# LED_Matrix_Driver_HT16K33_v1_0.net
KiCad netlist of a schematic drawn in EAGLE
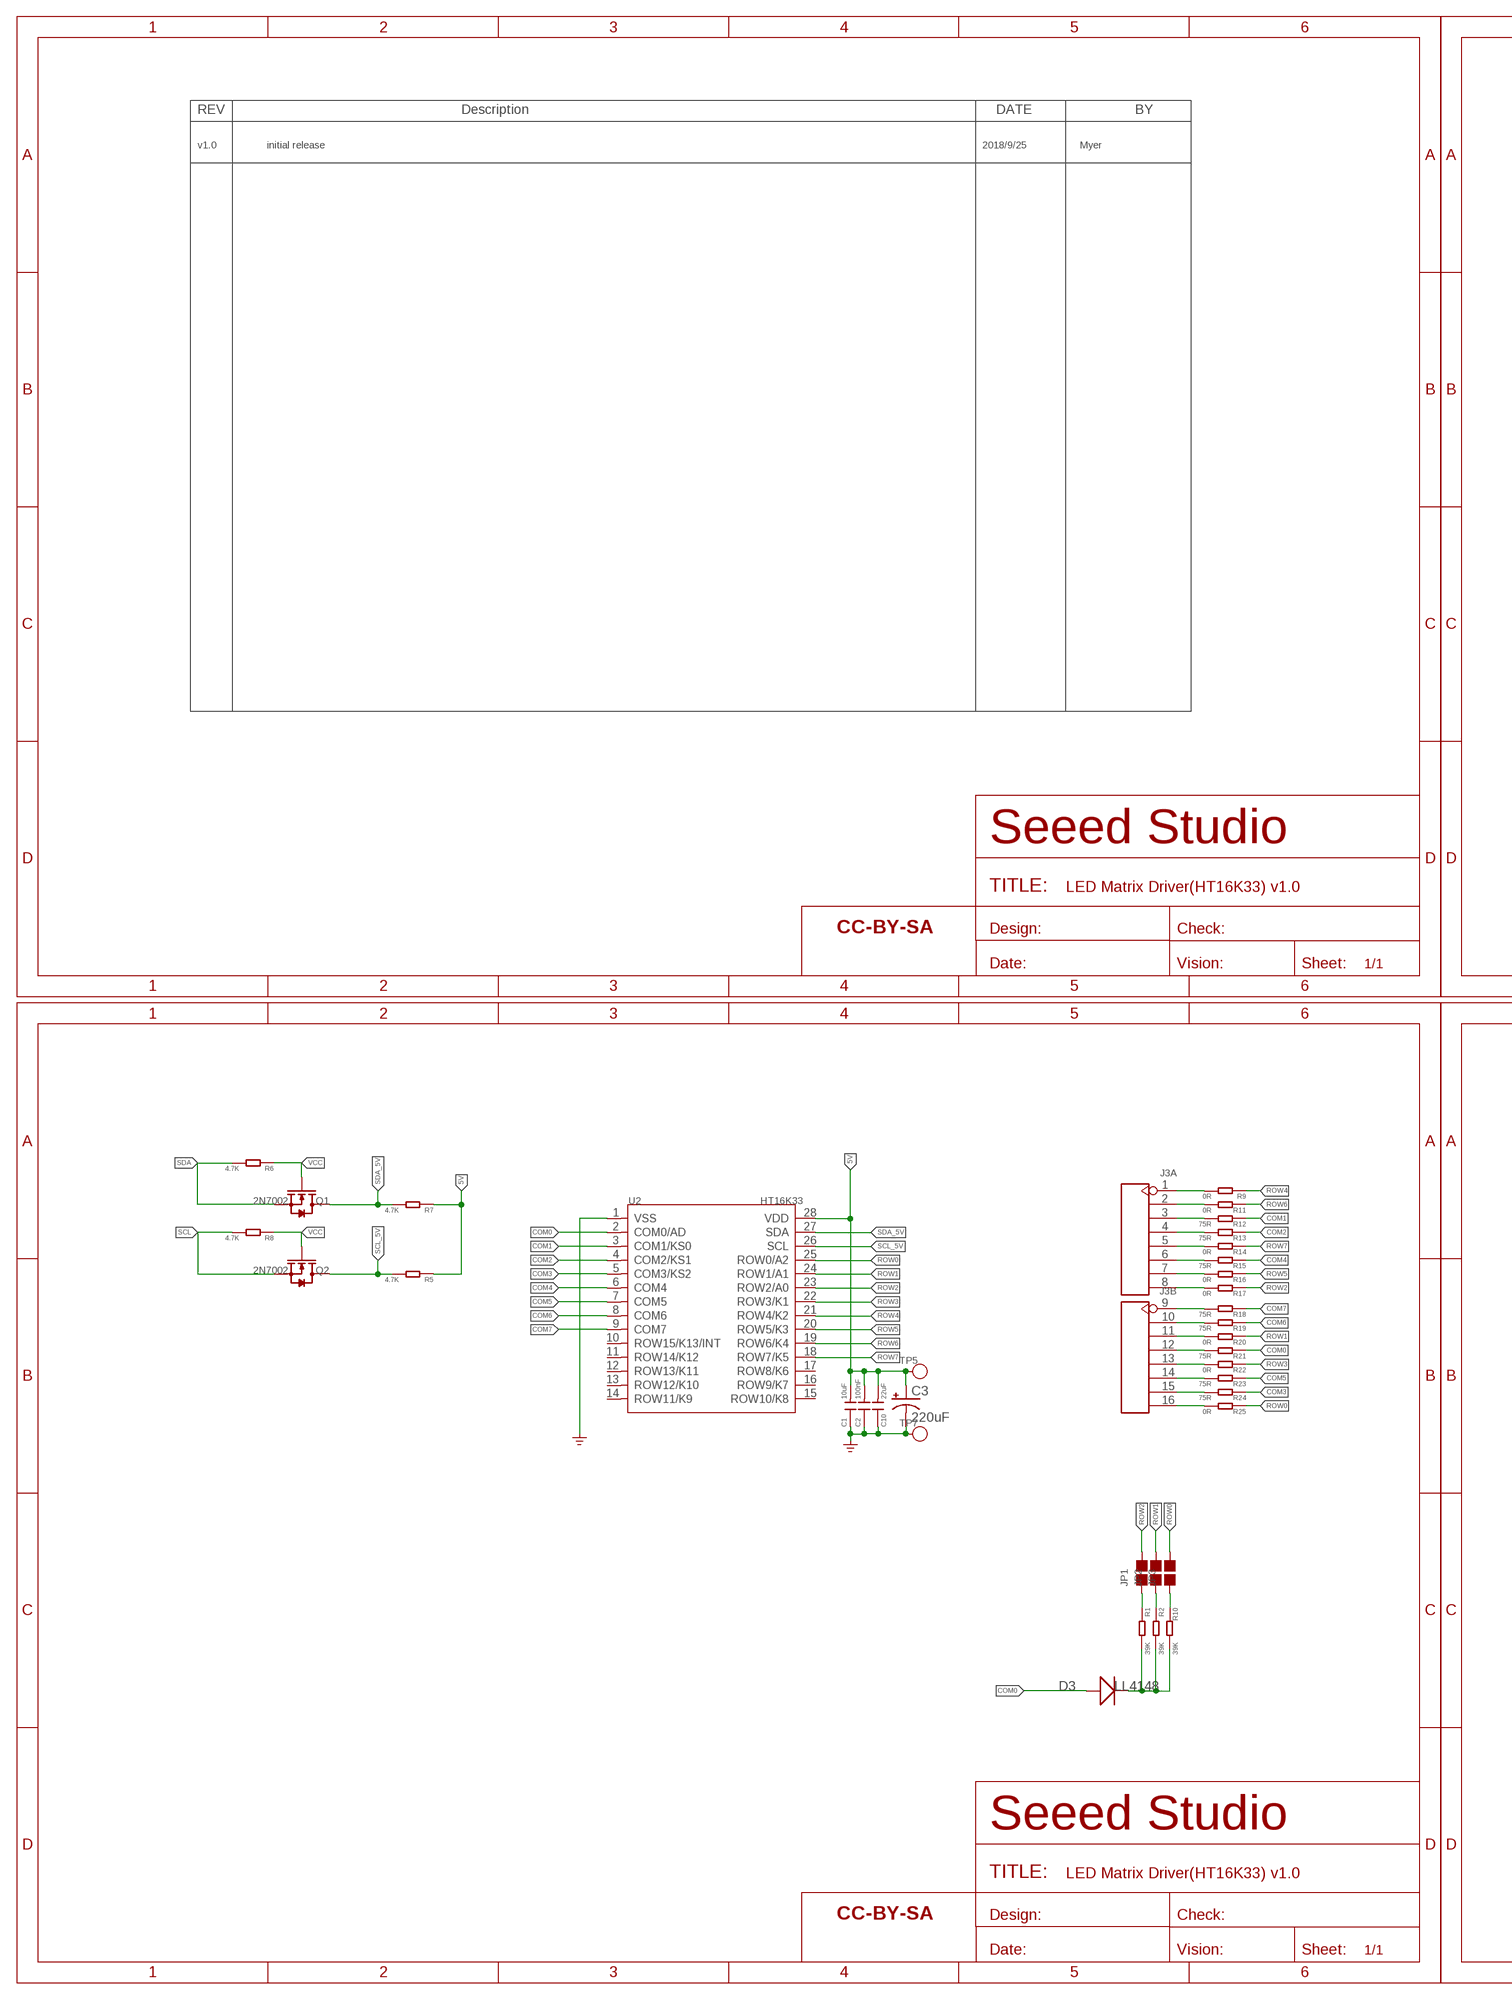
[diagram p0: schematic, sheet 1, part 1 of 2]
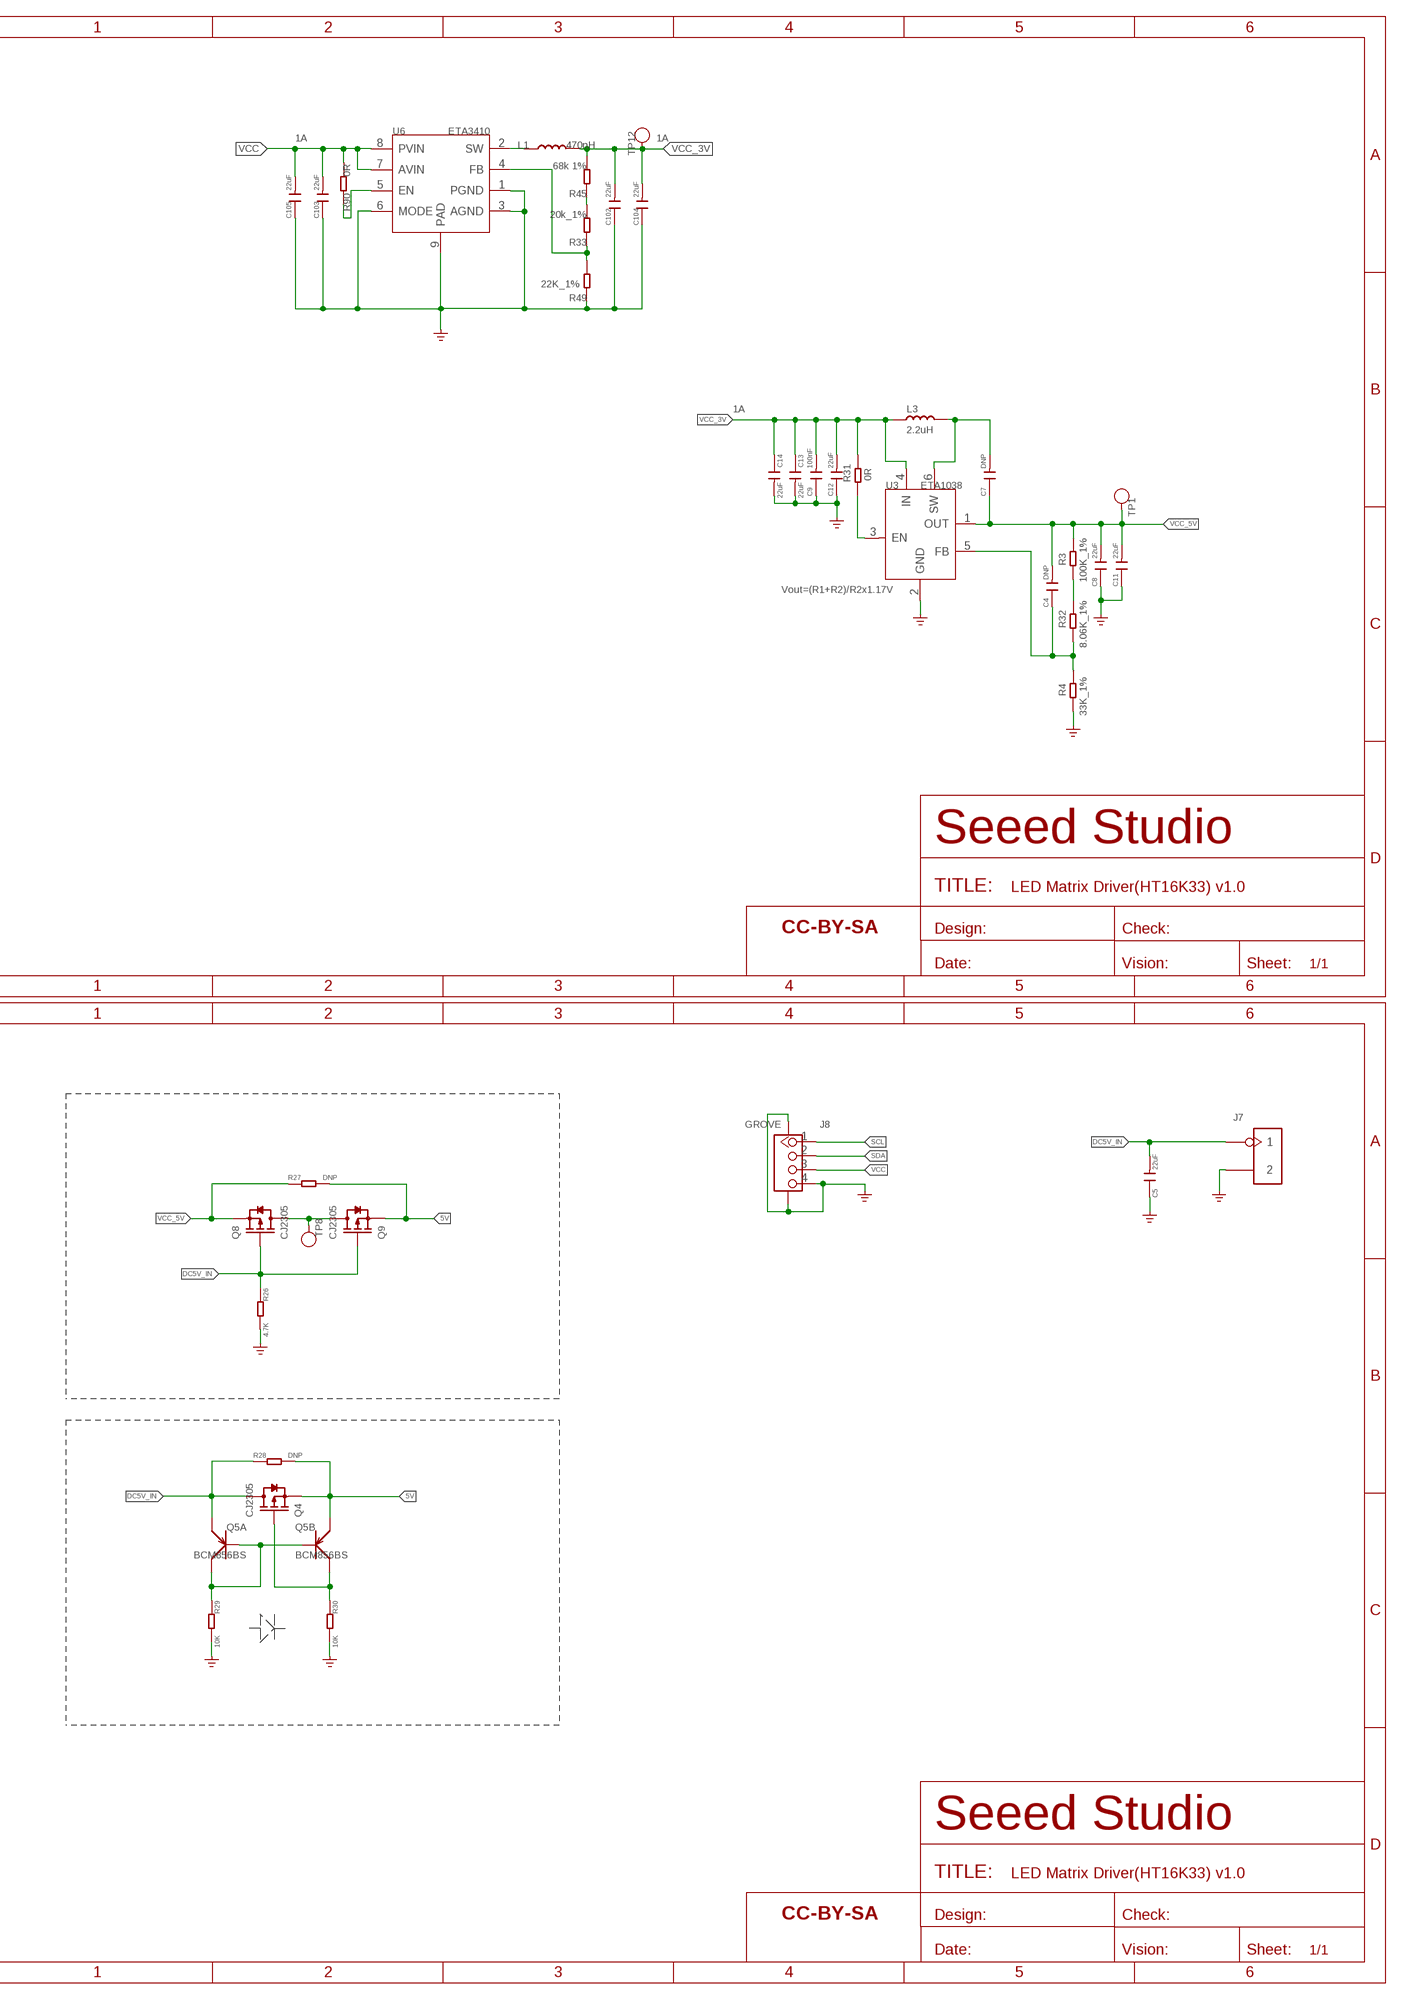
[diagram p1: schematic, sheet 1, part 2 of 2]

(export (version "E")
  (design (tool "Eeschema 10.0.6"))
  (components
    (comp (ref "C1")
      (value "10uF")
      (footprint "eagle-import:C0805")
      (libsource (lib "eagle-import") (part "C-0805"))
    )
    (comp (ref "C2")
      (value "100nF")
      (footprint "eagle-import:C0603")
      (libsource (lib "eagle-import") (part "C-0603"))
    )
    (comp (ref "C3")
      (value "220uF")
      (footprint "eagle-import:PANASONIC_D")
      (libsource (lib "eagle-import") (part "CPOL-USD"))
    )
    (comp (ref "C4")
      (value "DNP")
      (footprint "eagle-import:C0603")
      (libsource (lib "eagle-import") (part "C-0603"))
    )
    (comp (ref "C5")
      (value "22uF")
      (footprint "eagle-import:C0805")
      (libsource (lib "eagle-import") (part "C-0805"))
    )
    (comp (ref "C7")
      (value "DNP")
      (footprint "eagle-import:C0603")
      (libsource (lib "eagle-import") (part "C-0603"))
    )
    (comp (ref "C8")
      (value "22uF")
      (footprint "eagle-import:C0603")
      (libsource (lib "eagle-import") (part "C-0603"))
    )
    (comp (ref "C9")
      (value "100nF")
      (footprint "eagle-import:C0603")
      (libsource (lib "eagle-import") (part "C-0603"))
    )
    (comp (ref "C10")
      (value "22uF")
      (footprint "eagle-import:C0805")
      (libsource (lib "eagle-import") (part "C-0805"))
    )
    (comp (ref "C11")
      (value "22uF")
      (footprint "eagle-import:C0603")
      (libsource (lib "eagle-import") (part "C-0603"))
    )
    (comp (ref "C12")
      (value "22uF")
      (footprint "eagle-import:C0603")
      (libsource (lib "eagle-import") (part "C-0603"))
    )
    (comp (ref "C13")
      (value "22uF")
      (footprint "eagle-import:C0603")
      (libsource (lib "eagle-import") (part "C-0603"))
    )
    (comp (ref "C14")
      (value "22uF")
      (footprint "eagle-import:C0603")
      (libsource (lib "eagle-import") (part "C-0603"))
    )
    (comp (ref "C102")
      (value "22uF")
      (footprint "eagle-import:C0603")
      (libsource (lib "eagle-import") (part "C-0603"))
    )
    (comp (ref "C103")
      (value "22uF")
      (footprint "eagle-import:C0603")
      (libsource (lib "eagle-import") (part "C-0603"))
    )
    (comp (ref "C104")
      (value "22uF")
      (footprint "eagle-import:C0603")
      (libsource (lib "eagle-import") (part "C-0603"))
    )
    (comp (ref "C105")
      (value "22uF")
      (footprint "eagle-import:C0603")
      (libsource (lib "eagle-import") (part "C-0603"))
    )
    (comp (ref "D3")
      (value "LL4148")
      (footprint "eagle-import:DO-35-SMD")
      (libsource (lib "eagle-import") (part "D'1N4148-SMD'"))
    )
    (comp (ref "FR1")
      (value "SEEEDSTUDIO-OPEN-SCH-FRAME")
      (footprint "eagle-import:SEEEDSTUDIO-PCB-FRAME")
      (libsource (lib "eagle-import") (part "SEEEDSTUDIO-OPEN-SCH-FRAME"))
    )
    (comp (ref "FR2")
      (value "SEEEDSTUDIO-OPEN-SCH-FRAME")
      (footprint "eagle-import:SEEEDSTUDIO-PCB-FRAME")
      (libsource (lib "eagle-import") (part "SEEEDSTUDIO-OPEN-SCH-FRAME"))
    )
    (comp (ref "FR3")
      (value "SEEEDSTUDIO-OPEN-SCH-FRAME")
      (footprint "eagle-import:SEEEDSTUDIO-PCB-FRAME")
      (libsource (lib "eagle-import") (part "SEEEDSTUDIO-OPEN-SCH-FRAME"))
    )
    (comp (ref "J3")
      (value "HEADER-1X8PX2-LED-28.5MM")
      (footprint "eagle-import:H8X2-SMD-2.54-28.5MM")
      (libsource (lib "eagle-import") (part "HEADER-1X8PX2-LED-28.5MM"))
    )
    (comp (ref "J7")
      (value "HEADER-2P-65/35MIL")
      (footprint "eagle-import:H2-2.54")
      (libsource (lib "eagle-import") (part "HEADER-2P-65/35MIL"))
    )
    (comp (ref "J8")
      (value "GROVE")
      (footprint "eagle-import:HW4-SMD-2.0")
      (libsource (lib "eagle-import") (part "GROVE-CONNECTOR-SMD'DD'"))
    )
    (comp (ref "JP1")
      (value "JP-2P-NO")
      (footprint "eagle-import:2P-SMD-NO")
      (libsource (lib "eagle-import") (part "JP-2P-NO"))
    )
    (comp (ref "JP2")
      (value "JP-2P-NO")
      (footprint "eagle-import:2P-SMD-NO")
      (libsource (lib "eagle-import") (part "JP-2P-NO"))
    )
    (comp (ref "JP3")
      (value "JP-2P-NO")
      (footprint "eagle-import:2P-SMD-NO")
      (libsource (lib "eagle-import") (part "JP-2P-NO"))
    )
    (comp (ref "L1")
      (value "470nH")
      (footprint "eagle-import:L201610")
      (libsource (lib "eagle-import") (part "L-MPM201610SR33_T"))
    )
    (comp (ref "L3")
      (value "2.2uH")
      (footprint "eagle-import:L0806")
      (libsource (lib "eagle-import") (part "INDUCTOR/FERRITE-BEAD'0806'"))
    )
    (comp (ref "Q1")
      (value "2N7002")
      (footprint "eagle-import:SOT-23")
      (libsource (lib "eagle-import") (part "MOSFET-N'SOT23'"))
    )
    (comp (ref "Q2")
      (value "2N7002")
      (footprint "eagle-import:SOT-23")
      (libsource (lib "eagle-import") (part "MOSFET-N'SOT23'"))
    )
    (comp (ref "Q4")
      (value "CJ2305")
      (footprint "eagle-import:SOT-23")
      (libsource (lib "eagle-import") (part "MOSFET-P'SI2323CDS/SI2305DS{lt}BR{gt}'"))
    )
    (comp (ref "Q5")
      (value "BCM856BS")
      (footprint "eagle-import:SOT-363")
      (libsource (lib "eagle-import") (part "TRANSISTOR-DUAL-PNP"))
    )
    (comp (ref "Q8")
      (value "CJ2305")
      (footprint "eagle-import:SOT-23")
      (libsource (lib "eagle-import") (part "MOSFET-P'SI2323CDS/SI2305DS{lt}BR{gt}'"))
    )
    (comp (ref "Q9")
      (value "CJ2305")
      (footprint "eagle-import:SOT-23")
      (libsource (lib "eagle-import") (part "MOSFET-P'SI2323CDS/SI2305DS{lt}BR{gt}'"))
    )
    (comp (ref "R1")
      (value "39K")
      (footprint "eagle-import:R0603")
      (libsource (lib "eagle-import") (part "R-0603"))
    )
    (comp (ref "R2")
      (value "39K")
      (footprint "eagle-import:R0603")
      (libsource (lib "eagle-import") (part "R-0603"))
    )
    (comp (ref "R3")
      (value "100K_1%")
      (footprint "eagle-import:R0603")
      (libsource (lib "eagle-import") (part "R-0603"))
    )
    (comp (ref "R4")
      (value "33K_1%")
      (footprint "eagle-import:R0603")
      (libsource (lib "eagle-import") (part "R-0603"))
    )
    (comp (ref "R5")
      (value "4.7K")
      (footprint "eagle-import:R0603")
      (libsource (lib "eagle-import") (part "R-0603"))
    )
    (comp (ref "R6")
      (value "4.7K")
      (footprint "eagle-import:R0603")
      (libsource (lib "eagle-import") (part "R-0603"))
    )
    (comp (ref "R7")
      (value "4.7K")
      (footprint "eagle-import:R0603")
      (libsource (lib "eagle-import") (part "R-0603"))
    )
    (comp (ref "R8")
      (value "4.7K")
      (footprint "eagle-import:R0603")
      (libsource (lib "eagle-import") (part "R-0603"))
    )
    (comp (ref "R9")
      (value "0R")
      (footprint "eagle-import:R0603")
      (libsource (lib "eagle-import") (part "R-0603"))
    )
    (comp (ref "R10")
      (value "39K")
      (footprint "eagle-import:R0603")
      (libsource (lib "eagle-import") (part "R-0603"))
    )
    (comp (ref "R11")
      (value "0R")
      (footprint "eagle-import:R0603")
      (libsource (lib "eagle-import") (part "R-0603"))
    )
    (comp (ref "R12")
      (value "75R")
      (footprint "eagle-import:R0603")
      (libsource (lib "eagle-import") (part "R-0603"))
    )
    (comp (ref "R13")
      (value "75R")
      (footprint "eagle-import:R0603")
      (libsource (lib "eagle-import") (part "R-0603"))
    )
    (comp (ref "R14")
      (value "0R")
      (footprint "eagle-import:R0603")
      (libsource (lib "eagle-import") (part "R-0603"))
    )
    (comp (ref "R15")
      (value "75R")
      (footprint "eagle-import:R0603")
      (libsource (lib "eagle-import") (part "R-0603"))
    )
    (comp (ref "R16")
      (value "0R")
      (footprint "eagle-import:R0603")
      (libsource (lib "eagle-import") (part "R-0603"))
    )
    (comp (ref "R17")
      (value "0R")
      (footprint "eagle-import:R0603")
      (libsource (lib "eagle-import") (part "R-0603"))
    )
    (comp (ref "R18")
      (value "75R")
      (footprint "eagle-import:R0603")
      (libsource (lib "eagle-import") (part "R-0603"))
    )
    (comp (ref "R19")
      (value "75R")
      (footprint "eagle-import:R0603")
      (libsource (lib "eagle-import") (part "R-0603"))
    )
    (comp (ref "R20")
      (value "0R")
      (footprint "eagle-import:R0603")
      (libsource (lib "eagle-import") (part "R-0603"))
    )
    (comp (ref "R21")
      (value "75R")
      (footprint "eagle-import:R0603")
      (libsource (lib "eagle-import") (part "R-0603"))
    )
    (comp (ref "R22")
      (value "0R")
      (footprint "eagle-import:R0603")
      (libsource (lib "eagle-import") (part "R-0603"))
    )
    (comp (ref "R23")
      (value "75R")
      (footprint "eagle-import:R0603")
      (libsource (lib "eagle-import") (part "R-0603"))
    )
    (comp (ref "R24")
      (value "75R")
      (footprint "eagle-import:R0603")
      (libsource (lib "eagle-import") (part "R-0603"))
    )
    (comp (ref "R25")
      (value "0R")
      (footprint "eagle-import:R0603")
      (libsource (lib "eagle-import") (part "R-0603"))
    )
    (comp (ref "R26")
      (value "4.7K")
      (footprint "eagle-import:R0603")
      (libsource (lib "eagle-import") (part "R-0603"))
    )
    (comp (ref "R27")
      (value "DNP")
      (footprint "eagle-import:R0603")
      (libsource (lib "eagle-import") (part "R-0603"))
    )
    (comp (ref "R28")
      (value "DNP")
      (footprint "eagle-import:R0603")
      (libsource (lib "eagle-import") (part "R-0603"))
    )
    (comp (ref "R29")
      (value "10K")
      (footprint "eagle-import:R0603")
      (libsource (lib "eagle-import") (part "R-0603"))
    )
    (comp (ref "R30")
      (value "10K")
      (footprint "eagle-import:R0603")
      (libsource (lib "eagle-import") (part "R-0603"))
    )
    (comp (ref "R31")
      (value "0R")
      (footprint "eagle-import:R0603")
      (libsource (lib "eagle-import") (part "R-0603"))
    )
    (comp (ref "R32")
      (value "8.06K_1%")
      (footprint "eagle-import:R0603")
      (libsource (lib "eagle-import") (part "R-0603"))
    )
    (comp (ref "R33")
      (value "20k_1%")
      (footprint "eagle-import:R0603")
      (libsource (lib "eagle-import") (part "R-0603"))
    )
    (comp (ref "R45")
      (value "68k 1%")
      (footprint "eagle-import:R0603")
      (libsource (lib "eagle-import") (part "R-0603"))
    )
    (comp (ref "R49")
      (value "22K_1%")
      (footprint "eagle-import:R0603")
      (libsource (lib "eagle-import") (part "R-0603"))
    )
    (comp (ref "R90")
      (value "0R")
      (footprint "eagle-import:R0603")
      (libsource (lib "eagle-import") (part "R-0603"))
    )
    (comp (ref "TP1")
      (value "TEST-POINT'4545'")
      (footprint "eagle-import:TP-D45MIL")
      (fields (field (name "PARTNO") "DNP"))
      (libsource (lib "eagle-import") (part "TEST-POINT'4545'"))
    )
    (comp (ref "TP5")
      (value "TEST-POINT'4545'")
      (footprint "eagle-import:TP-D45MIL")
      (fields (field (name "PARTNO") "DNP"))
      (libsource (lib "eagle-import") (part "TEST-POINT'4545'"))
    )
    (comp (ref "TP7")
      (value "TEST-POINT'4545'")
      (footprint "eagle-import:TP-D45MIL")
      (fields (field (name "PARTNO") "DNP"))
      (libsource (lib "eagle-import") (part "TEST-POINT'4545'"))
    )
    (comp (ref "TP8")
      (value "TEST-POINT'4545'")
      (footprint "eagle-import:TP-D45MIL")
      (fields (field (name "PARTNO") "DNP"))
      (libsource (lib "eagle-import") (part "TEST-POINT'4545'"))
    )
    (comp (ref "TP12")
      (value "TEST-POINT'4545'")
      (footprint "eagle-import:TP-D45MIL")
      (fields (field (name "PARTNO") "DNP"))
      (libsource (lib "eagle-import") (part "TEST-POINT'4545'"))
    )
    (comp (ref "U$1")
      (value "SEEEDSTUDIO-OPEN-SCH-FRAME")
      (footprint "eagle-import:SEEEDSTUDIO-PCB-FRAME")
      (libsource (lib "eagle-import") (part "SEEEDSTUDIO-OPEN-SCH-FRAME"))
    )
    (comp (ref "U2")
      (value "HT16K33")
      (footprint "eagle-import:SOP28-1.27-18.2X7.4MM")
      (libsource (lib "eagle-import") (part "DRIVER-HT16K33-28P"))
    )
    (comp (ref "U3")
      (value "ETA1038")
      (footprint "eagle-import:SOT-23-6")
      (libsource (lib "eagle-import") (part "CONVERTER-ETA1038"))
    )
    (comp (ref "U6")
      (value "ETA3410")
      (footprint "eagle-import:DFN8G-0.5-2X2MM")
      (libsource (lib "eagle-import") (part "CONVERTER-ETA3410"))
    )
  )
  (nets
    (net (code "1") (name "5V") (class "Default")
      (node (ref "C1") (pin "2") (pinfunction "2_2") (pintype "passive"))
      (node (ref "C10") (pin "2") (pinfunction "2_2") (pintype "passive"))
      (node (ref "C2") (pin "2") (pinfunction "2_2") (pintype "passive"))
      (node (ref "C3") (pin "+") (pinfunction "+_+") (pintype "passive"))
      (node (ref "Q4") (pin "2") (pinfunction "S_2") (pintype "passive"))
      (node (ref "Q5") (pin "4") (pinfunction "E_4") (pintype "passive"))
      (node (ref "Q9") (pin "2") (pinfunction "S_2") (pintype "passive"))
      (node (ref "R27") (pin "2") (pinfunction "2_2") (pintype "passive"))
      (node (ref "R28") (pin "2") (pinfunction "2_2") (pintype "passive"))
      (node (ref "R5") (pin "1") (pinfunction "1_1") (pintype "passive"))
      (node (ref "R7") (pin "1") (pinfunction "1_1") (pintype "passive"))
      (node (ref "TP5") (pin "T") (pinfunction "T_T") (pintype "bidirectional"))
      (node (ref "U2") (pin "28") (pinfunction "VDD_28") (pintype "bidirectional"))
    )
    (net (code "2") (name "COM0") (class "Default")
      (node (ref "D3") (pin "A") (pinfunction "+_A") (pintype "passive"))
      (node (ref "R21") (pin "1") (pinfunction "1_1") (pintype "passive"))
      (node (ref "U2") (pin "2") (pinfunction "COM0/AD_2") (pintype "bidirectional"))
    )
    (net (code "3") (name "COM1") (class "Default")
      (node (ref "R12") (pin "1") (pinfunction "1_1") (pintype "passive"))
      (node (ref "U2") (pin "3") (pinfunction "COM1/KS0_3") (pintype "bidirectional"))
    )
    (net (code "4") (name "COM2") (class "Default")
      (node (ref "R13") (pin "1") (pinfunction "1_1") (pintype "passive"))
      (node (ref "U2") (pin "4") (pinfunction "COM2/KS1_4") (pintype "bidirectional"))
    )
    (net (code "5") (name "COM3") (class "Default")
      (node (ref "R24") (pin "1") (pinfunction "1_1") (pintype "passive"))
      (node (ref "U2") (pin "5") (pinfunction "COM3/KS2_5") (pintype "bidirectional"))
    )
    (net (code "6") (name "COM4") (class "Default")
      (node (ref "R15") (pin "1") (pinfunction "1_1") (pintype "passive"))
      (node (ref "U2") (pin "6") (pinfunction "COM4_6") (pintype "bidirectional"))
    )
    (net (code "7") (name "COM5") (class "Default")
      (node (ref "R23") (pin "1") (pinfunction "1_1") (pintype "passive"))
      (node (ref "U2") (pin "7") (pinfunction "COM5_7") (pintype "bidirectional"))
    )
    (net (code "8") (name "COM6") (class "Default")
      (node (ref "R19") (pin "1") (pinfunction "1_1") (pintype "passive"))
      (node (ref "U2") (pin "8") (pinfunction "COM6_8") (pintype "bidirectional"))
    )
    (net (code "9") (name "COM7") (class "Default")
      (node (ref "R18") (pin "1") (pinfunction "1_1") (pintype "passive"))
      (node (ref "U2") (pin "9") (pinfunction "COM7_9") (pintype "bidirectional"))
    )
    (net (code "10") (name "DC5V_IN") (class "Default")
      (node (ref "C5") (pin "2") (pinfunction "2_2") (pintype "passive"))
      (node (ref "J7") (pin "1") (pinfunction "1_1") (pintype "bidirectional"))
      (node (ref "Q4") (pin "3") (pinfunction "D_3") (pintype "passive"))
      (node (ref "Q5") (pin "1") (pinfunction "E_1") (pintype "passive"))
      (node (ref "Q8") (pin "1") (pinfunction "G_1") (pintype "passive"))
      (node (ref "Q9") (pin "1") (pinfunction "G_1") (pintype "passive"))
      (node (ref "R26") (pin "1") (pinfunction "1_1") (pintype "passive"))
      (node (ref "R28") (pin "1") (pinfunction "1_1") (pintype "passive"))
    )
    (net (code "11") (name "GND_POWER") (class "Default")
      (node (ref "C1") (pin "1") (pinfunction "1_1") (pintype "passive"))
      (node (ref "C10") (pin "1") (pinfunction "1_1") (pintype "passive"))
      (node (ref "C102") (pin "1") (pinfunction "1_1") (pintype "passive"))
      (node (ref "C103") (pin "1") (pinfunction "1_1") (pintype "passive"))
      (node (ref "C104") (pin "1") (pinfunction "1_1") (pintype "passive"))
      (node (ref "C105") (pin "1") (pinfunction "1_1") (pintype "passive"))
      (node (ref "C11") (pin "1") (pinfunction "1_1") (pintype "passive"))
      (node (ref "C12") (pin "1") (pinfunction "1_1") (pintype "passive"))
      (node (ref "C13") (pin "2") (pinfunction "2_2") (pintype "passive"))
      (node (ref "C14") (pin "2") (pinfunction "2_2") (pintype "passive"))
      (node (ref "C2") (pin "1") (pinfunction "1_1") (pintype "passive"))
      (node (ref "C3") (pin "-") (pinfunction "-_-") (pintype "passive"))
      (node (ref "C5") (pin "1") (pinfunction "1_1") (pintype "passive"))
      (node (ref "C8") (pin "1") (pinfunction "1_1") (pintype "passive"))
      (node (ref "C9") (pin "1") (pinfunction "1_1") (pintype "passive"))
      (node (ref "J7") (pin "2") (pinfunction "2_2") (pintype "bidirectional"))
      (node (ref "J8") (pin "4") (pinfunction "4_4") (pintype "bidirectional"))
      (node (ref "J8") (pin "SS1") (pinfunction "SS1_SS1") (pintype "bidirectional"))
      (node (ref "J8") (pin "SS2") (pinfunction "SS2_SS2") (pintype "bidirectional"))
      (node (ref "R26") (pin "2") (pinfunction "2_2") (pintype "passive"))
      (node (ref "R29") (pin "2") (pinfunction "2_2") (pintype "passive"))
      (node (ref "R30") (pin "2") (pinfunction "2_2") (pintype "passive"))
      (node (ref "R4") (pin "1") (pinfunction "1_1") (pintype "passive"))
      (node (ref "R49") (pin "1") (pinfunction "1_1") (pintype "passive"))
      (node (ref "TP7") (pin "T") (pinfunction "T_T") (pintype "bidirectional"))
      (node (ref "U2") (pin "1") (pinfunction "VSS_1") (pintype "bidirectional"))
      (node (ref "U3") (pin "2") (pinfunction "GND_2") (pintype "bidirectional"))
      (node (ref "U6") (pin "1") (pinfunction "PGND_1") (pintype "bidirectional"))
      (node (ref "U6") (pin "3") (pinfunction "AGND_3") (pintype "bidirectional"))
      (node (ref "U6") (pin "6") (pinfunction "MODE_6") (pintype "bidirectional"))
      (node (ref "U6") (pin "9") (pinfunction "PAD_9") (pintype "bidirectional"))
    )
    (net (code "12") (name "Net-(D3--)") (class "Default")
      (node (ref "D3") (pin "C") (pinfunction "-_C") (pintype "passive"))
      (node (ref "R1") (pin "2") (pinfunction "2_2") (pintype "passive"))
      (node (ref "R10") (pin "2") (pinfunction "2_2") (pintype "passive"))
      (node (ref "R2") (pin "2") (pinfunction "2_2") (pintype "passive"))
    )
    (net (code "13") (name "Net-(J3-Pad1)") (class "Default")
      (node (ref "J3") (pin "1") (pinfunction "1_1") (pintype "bidirectional"))
      (node (ref "R9") (pin "2") (pinfunction "2_2") (pintype "passive"))
    )
    (net (code "14") (name "Net-(J3-Pad2)") (class "Default")
      (node (ref "J3") (pin "2") (pinfunction "2_2") (pintype "bidirectional"))
      (node (ref "R11") (pin "2") (pinfunction "2_2") (pintype "passive"))
    )
    (net (code "15") (name "Net-(J3-Pad3)") (class "Default")
      (node (ref "J3") (pin "3") (pinfunction "3_3") (pintype "bidirectional"))
      (node (ref "R12") (pin "2") (pinfunction "2_2") (pintype "passive"))
    )
    (net (code "16") (name "Net-(J3-Pad4)") (class "Default")
      (node (ref "J3") (pin "4") (pinfunction "4_4") (pintype "bidirectional"))
      (node (ref "R13") (pin "2") (pinfunction "2_2") (pintype "passive"))
    )
    (net (code "17") (name "Net-(J3-Pad5)") (class "Default")
      (node (ref "J3") (pin "5") (pinfunction "5_5") (pintype "bidirectional"))
      (node (ref "R14") (pin "2") (pinfunction "2_2") (pintype "passive"))
    )
    (net (code "18") (name "Net-(J3-Pad6)") (class "Default")
      (node (ref "J3") (pin "6") (pinfunction "6_6") (pintype "bidirectional"))
      (node (ref "R15") (pin "2") (pinfunction "2_2") (pintype "passive"))
    )
    (net (code "19") (name "Net-(J3-Pad7)") (class "Default")
      (node (ref "J3") (pin "7") (pinfunction "7_7") (pintype "bidirectional"))
      (node (ref "R16") (pin "2") (pinfunction "2_2") (pintype "passive"))
    )
    (net (code "20") (name "Net-(J3-Pad8)") (class "Default")
      (node (ref "J3") (pin "8") (pinfunction "8_8") (pintype "bidirectional"))
      (node (ref "R17") (pin "2") (pinfunction "2_2") (pintype "passive"))
    )
    (net (code "21") (name "Net-(J3B-1)") (class "Default")
      (node (ref "J3") (pin "9") (pinfunction "1_9") (pintype "bidirectional"))
      (node (ref "R18") (pin "2") (pinfunction "2_2") (pintype "passive"))
    )
    (net (code "22") (name "Net-(J3B-2)") (class "Default")
      (node (ref "J3") (pin "10") (pinfunction "2_10") (pintype "bidirectional"))
      (node (ref "R19") (pin "2") (pinfunction "2_2") (pintype "passive"))
    )
    (net (code "23") (name "Net-(J3B-3)") (class "Default")
      (node (ref "J3") (pin "11") (pinfunction "3_11") (pintype "bidirectional"))
      (node (ref "R20") (pin "2") (pinfunction "2_2") (pintype "passive"))
    )
    (net (code "24") (name "Net-(J3B-4)") (class "Default")
      (node (ref "J3") (pin "12") (pinfunction "4_12") (pintype "bidirectional"))
      (node (ref "R21") (pin "2") (pinfunction "2_2") (pintype "passive"))
    )
    (net (code "25") (name "Net-(J3B-5)") (class "Default")
      (node (ref "J3") (pin "13") (pinfunction "5_13") (pintype "bidirectional"))
      (node (ref "R22") (pin "2") (pinfunction "2_2") (pintype "passive"))
    )
    (net (code "26") (name "Net-(J3B-6)") (class "Default")
      (node (ref "J3") (pin "14") (pinfunction "6_14") (pintype "bidirectional"))
      (node (ref "R23") (pin "2") (pinfunction "2_2") (pintype "passive"))
    )
    (net (code "27") (name "Net-(J3B-7)") (class "Default")
      (node (ref "J3") (pin "15") (pinfunction "7_15") (pintype "bidirectional"))
      (node (ref "R24") (pin "2") (pinfunction "2_2") (pintype "passive"))
    )
    (net (code "28") (name "Net-(J3B-8)") (class "Default")
      (node (ref "J3") (pin "16") (pinfunction "8_16") (pintype "bidirectional"))
      (node (ref "R25") (pin "2") (pinfunction "2_2") (pintype "passive"))
    )
    (net (code "29") (name "Net-(JP1-Pad1)") (class "Default")
      (node (ref "JP1") (pin "1") (pinfunction "1_1") (pintype "bidirectional"))
      (node (ref "R1") (pin "1") (pinfunction "1_1") (pintype "passive"))
    )
    (net (code "30") (name "Net-(JP2-Pad1)") (class "Default")
      (node (ref "JP2") (pin "1") (pinfunction "1_1") (pintype "bidirectional"))
      (node (ref "R2") (pin "1") (pinfunction "1_1") (pintype "passive"))
    )
    (net (code "31") (name "Net-(JP3-Pad1)") (class "Default")
      (node (ref "JP3") (pin "1") (pinfunction "1_1") (pintype "bidirectional"))
      (node (ref "R10") (pin "1") (pinfunction "1_1") (pintype "passive"))
    )
    (net (code "32") (name "Net-(Q4-G)") (class "Default")
      (node (ref "Q4") (pin "1") (pinfunction "G_1") (pintype "passive"))
      (node (ref "Q5") (pin "3") (pinfunction "C_3") (pintype "passive"))
      (node (ref "R30") (pin "1") (pinfunction "1_1") (pintype "passive"))
    )
    (net (code "33") (name "Net-(Q5A-B)") (class "Default")
      (node (ref "Q5") (pin "2") (pinfunction "B_2") (pintype "passive"))
      (node (ref "Q5") (pin "5") (pinfunction "B_5") (pintype "passive"))
      (node (ref "Q5") (pin "6") (pinfunction "C_6") (pintype "passive"))
      (node (ref "R29") (pin "1") (pinfunction "1_1") (pintype "passive"))
    )
    (net (code "34") (name "Net-(Q8-D)") (class "Default")
      (node (ref "Q8") (pin "3") (pinfunction "D_3") (pintype "passive"))
      (node (ref "Q9") (pin "3") (pinfunction "D_3") (pintype "passive"))
      (node (ref "TP8") (pin "T") (pinfunction "T_T") (pintype "bidirectional"))
    )
    (net (code "35") (name "Net-(R3-Pad2)") (class "Default")
      (node (ref "R3") (pin "2") (pinfunction "2_2") (pintype "passive"))
      (node (ref "R32") (pin "1") (pinfunction "1_1") (pintype "passive"))
    )
    (net (code "36") (name "Net-(R33-Pad2)") (class "Default")
      (node (ref "R33") (pin "2") (pinfunction "2_2") (pintype "passive"))
      (node (ref "R45") (pin "1") (pinfunction "1_1") (pintype "passive"))
    )
    (net (code "37") (name "Net-(U3-EN)") (class "Default")
      (node (ref "R31") (pin "2") (pinfunction "2_2") (pintype "passive"))
      (node (ref "U3") (pin "3") (pinfunction "EN_3") (pintype "bidirectional"))
    )
    (net (code "38") (name "Net-(U3-FB)") (class "Default")
      (node (ref "C4") (pin "1") (pinfunction "1_1") (pintype "passive"))
      (node (ref "R32") (pin "2") (pinfunction "2_2") (pintype "passive"))
      (node (ref "R4") (pin "2") (pinfunction "2_2") (pintype "passive"))
      (node (ref "U3") (pin "5") (pinfunction "FB_5") (pintype "bidirectional"))
    )
    (net (code "39") (name "Net-(U3-SW)") (class "Default")
      (node (ref "C7") (pin "2") (pinfunction "2_2") (pintype "passive"))
      (node (ref "L3") (pin "2") (pinfunction "2_2") (pintype "passive"))
      (node (ref "U3") (pin "6") (pinfunction "SW_6") (pintype "bidirectional"))
    )
    (net (code "40") (name "Net-(U6-EN)") (class "Default")
      (node (ref "R90") (pin "1") (pinfunction "1_1") (pintype "passive"))
      (node (ref "U6") (pin "5") (pinfunction "EN_5") (pintype "bidirectional"))
    )
    (net (code "41") (name "Net-(U6-FB)") (class "Default")
      (node (ref "R33") (pin "1") (pinfunction "1_1") (pintype "passive"))
      (node (ref "R49") (pin "2") (pinfunction "2_2") (pintype "passive"))
      (node (ref "U6") (pin "4") (pinfunction "FB_4") (pintype "bidirectional"))
    )
    (net (code "42") (name "Net-(U6-SW)") (class "Default")
      (node (ref "L1") (pin "1") (pinfunction "1_1") (pintype "passive"))
      (node (ref "U6") (pin "2") (pinfunction "SW_2") (pintype "bidirectional"))
    )
    (net (code "43") (name "ROW0") (class "Default")
      (node (ref "JP3") (pin "2") (pinfunction "2_2") (pintype "bidirectional"))
      (node (ref "R25") (pin "1") (pinfunction "1_1") (pintype "passive"))
      (node (ref "U2") (pin "25") (pinfunction "ROW0/A2_25") (pintype "bidirectional"))
    )
    (net (code "44") (name "ROW1") (class "Default")
      (node (ref "JP2") (pin "2") (pinfunction "2_2") (pintype "bidirectional"))
      (node (ref "R20") (pin "1") (pinfunction "1_1") (pintype "passive"))
      (node (ref "U2") (pin "24") (pinfunction "ROW1/A1_24") (pintype "bidirectional"))
    )
    (net (code "45") (name "ROW2") (class "Default")
      (node (ref "JP1") (pin "2") (pinfunction "2_2") (pintype "bidirectional"))
      (node (ref "R17") (pin "1") (pinfunction "1_1") (pintype "passive"))
      (node (ref "U2") (pin "23") (pinfunction "ROW2/A0_23") (pintype "bidirectional"))
    )
    (net (code "46") (name "ROW3") (class "Default")
      (node (ref "R22") (pin "1") (pinfunction "1_1") (pintype "passive"))
      (node (ref "U2") (pin "22") (pinfunction "ROW3/K1_22") (pintype "bidirectional"))
    )
    (net (code "47") (name "ROW4") (class "Default")
      (node (ref "R9") (pin "1") (pinfunction "1_1") (pintype "passive"))
      (node (ref "U2") (pin "21") (pinfunction "ROW4/K2_21") (pintype "bidirectional"))
    )
    (net (code "48") (name "ROW5") (class "Default")
      (node (ref "R16") (pin "1") (pinfunction "1_1") (pintype "passive"))
      (node (ref "U2") (pin "20") (pinfunction "ROW5/K3_20") (pintype "bidirectional"))
    )
    (net (code "49") (name "ROW6") (class "Default")
      (node (ref "R11") (pin "1") (pinfunction "1_1") (pintype "passive"))
      (node (ref "U2") (pin "19") (pinfunction "ROW6/K4_19") (pintype "bidirectional"))
    )
    (net (code "50") (name "ROW7") (class "Default")
      (node (ref "R14") (pin "1") (pinfunction "1_1") (pintype "passive"))
      (node (ref "U2") (pin "18") (pinfunction "ROW7/K5_18") (pintype "bidirectional"))
    )
    (net (code "51") (name "SCL") (class "Default")
      (node (ref "J8") (pin "1") (pinfunction "1_1") (pintype "bidirectional"))
      (node (ref "Q2") (pin "2") (pinfunction "S_2") (pintype "passive"))
      (node (ref "R8") (pin "2") (pinfunction "2_2") (pintype "passive"))
    )
    (net (code "52") (name "SCL_5V") (class "Default")
      (node (ref "Q2") (pin "3") (pinfunction "D_3") (pintype "passive"))
      (node (ref "R5") (pin "2") (pinfunction "2_2") (pintype "passive"))
      (node (ref "U2") (pin "26") (pinfunction "SCL_26") (pintype "bidirectional"))
    )
    (net (code "53") (name "SDA") (class "Default")
      (node (ref "J8") (pin "2") (pinfunction "2_2") (pintype "bidirectional"))
      (node (ref "Q1") (pin "2") (pinfunction "S_2") (pintype "passive"))
      (node (ref "R6") (pin "2") (pinfunction "2_2") (pintype "passive"))
    )
    (net (code "54") (name "SDA_5V") (class "Default")
      (node (ref "Q1") (pin "3") (pinfunction "D_3") (pintype "passive"))
      (node (ref "R7") (pin "2") (pinfunction "2_2") (pintype "passive"))
      (node (ref "U2") (pin "27") (pinfunction "SDA_27") (pintype "bidirectional"))
    )
    (net (code "55") (name "VCC") (class "Default")
      (node (ref "C103") (pin "2") (pinfunction "2_2") (pintype "passive"))
      (node (ref "C105") (pin "2") (pinfunction "2_2") (pintype "passive"))
      (node (ref "J8") (pin "3") (pinfunction "3_3") (pintype "bidirectional"))
      (node (ref "Q1") (pin "1") (pinfunction "G_1") (pintype "passive"))
      (node (ref "Q2") (pin "1") (pinfunction "G_1") (pintype "passive"))
      (node (ref "R6") (pin "1") (pinfunction "1_1") (pintype "passive"))
      (node (ref "R8") (pin "1") (pinfunction "1_1") (pintype "passive"))
      (node (ref "R90") (pin "2") (pinfunction "2_2") (pintype "passive"))
      (node (ref "U6") (pin "7") (pinfunction "AVIN_7") (pintype "bidirectional"))
      (node (ref "U6") (pin "8") (pinfunction "PVIN_8") (pintype "bidirectional"))
    )
    (net (code "56") (name "VCC_3V") (class "Default")
      (node (ref "C102") (pin "2") (pinfunction "2_2") (pintype "passive"))
      (node (ref "C104") (pin "2") (pinfunction "2_2") (pintype "passive"))
      (node (ref "C12") (pin "2") (pinfunction "2_2") (pintype "passive"))
      (node (ref "C13") (pin "1") (pinfunction "1_1") (pintype "passive"))
      (node (ref "C14") (pin "1") (pinfunction "1_1") (pintype "passive"))
      (node (ref "C9") (pin "2") (pinfunction "2_2") (pintype "passive"))
      (node (ref "L1") (pin "2") (pinfunction "2_2") (pintype "passive"))
      (node (ref "L3") (pin "1") (pinfunction "1_1") (pintype "passive"))
      (node (ref "R31") (pin "1") (pinfunction "1_1") (pintype "passive"))
      (node (ref "R45") (pin "2") (pinfunction "2_2") (pintype "passive"))
      (node (ref "TP12") (pin "T") (pinfunction "T_T") (pintype "bidirectional"))
      (node (ref "U3") (pin "4") (pinfunction "IN_4") (pintype "bidirectional"))
    )
    (net (code "57") (name "VCC_5V") (class "Default")
      (node (ref "C11") (pin "2") (pinfunction "2_2") (pintype "passive"))
      (node (ref "C4") (pin "2") (pinfunction "2_2") (pintype "passive"))
      (node (ref "C7") (pin "1") (pinfunction "1_1") (pintype "passive"))
      (node (ref "C8") (pin "2") (pinfunction "2_2") (pintype "passive"))
      (node (ref "Q8") (pin "2") (pinfunction "S_2") (pintype "passive"))
      (node (ref "R27") (pin "1") (pinfunction "1_1") (pintype "passive"))
      (node (ref "R3") (pin "1") (pinfunction "1_1") (pintype "passive"))
      (node (ref "TP1") (pin "T") (pinfunction "T_T") (pintype "bidirectional"))
      (node (ref "U3") (pin "1") (pinfunction "OUT_1") (pintype "bidirectional"))
    )
    (net (code "58") (name "unconnected-(U2-ROW8{slash}K6-Pad17)") (class "Default")
      (node (ref "U2") (pin "17") (pinfunction "ROW8/K6_17") (pintype "bidirectional"))
    )
    (net (code "59") (name "unconnected-(U2-ROW9{slash}K7-Pad16)") (class "Default")
      (node (ref "U2") (pin "16") (pinfunction "ROW9/K7_16") (pintype "bidirectional"))
    )
    (net (code "60") (name "unconnected-(U2-ROW10{slash}K8-Pad15)") (class "Default")
      (node (ref "U2") (pin "15") (pinfunction "ROW10/K8_15") (pintype "bidirectional"))
    )
    (net (code "61") (name "unconnected-(U2-ROW11{slash}K9-Pad14)") (class "Default")
      (node (ref "U2") (pin "14") (pinfunction "ROW11/K9_14") (pintype "bidirectional"))
    )
    (net (code "62") (name "unconnected-(U2-ROW12{slash}K10-Pad13)") (class "Default")
      (node (ref "U2") (pin "13") (pinfunction "ROW12/K10_13") (pintype "bidirectional"))
    )
    (net (code "63") (name "unconnected-(U2-ROW13{slash}K11-Pad12)") (class "Default")
      (node (ref "U2") (pin "12") (pinfunction "ROW13/K11_12") (pintype "bidirectional"))
    )
    (net (code "64") (name "unconnected-(U2-ROW14{slash}K12-Pad11)") (class "Default")
      (node (ref "U2") (pin "11") (pinfunction "ROW14/K12_11") (pintype "bidirectional"))
    )
    (net (code "65") (name "unconnected-(U2-ROW15{slash}K13{slash}INT-Pad10)") (class "Default")
      (node (ref "U2") (pin "10") (pinfunction "ROW15/K13/INT_10") (pintype "bidirectional"))
    )
  )
)
